# SHT1x.net
KiCad netlist of a schematic drawn in Altium Designer
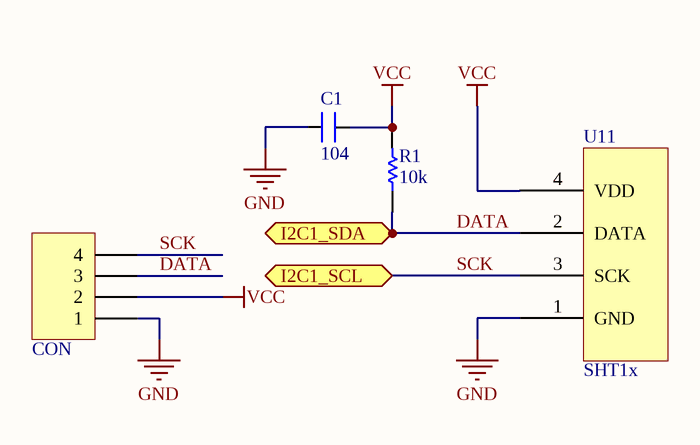
[diagram p0: SHT1x.SchDoc]

(export (version "E")
  (design (tool "Eeschema 10.0.6"))
  (components
    (comp (ref "C1")
      (value "104")
      (footprint "CAPC1608N")
      (fields (field (name "Comment") "CAP NP"))
      (libsource (lib "Tuan") (part "CAP NP"))
    )
    (comp (ref "CON")
      (value "Header 4H")
      (footprint "heromap:HDR1X4H")
      (description "Header, 4-Pin, Right Angle")
      (fields (field (name "PUBLISHER") "Altium Limited"))
      (libsource (lib "heromap") (part "Header 4H"))
    )
    (comp (ref "R1")
      (value "10k")
      (footprint "RESC2012N_F")
      (fields (field (name "Comment") "Res"))
      (libsource (lib "Tuan") (part "Res"))
    )
    (comp (ref "U11") (value "SHT1x") (footprint "SHT1x") (libsource (lib "Tuan") (part "SHT1x")))
  )
  (nets
    (net (code "1") (name "/DATA") (class "Default")
      (node (ref "CON") (pin "3") (pinfunction "3_3") (pintype "passive"))
      (node (ref "R1") (pin "1") (pinfunction "1_1") (pintype "passive"))
      (node (ref "U11") (pin "2") (pinfunction "DATA_2") (pintype "passive"))
    )
    (net (code "2") (name "/SCK") (class "Default")
      (node (ref "CON") (pin "4") (pinfunction "4_4") (pintype "passive"))
      (node (ref "U11") (pin "3") (pinfunction "SCK_3") (pintype "passive"))
    )
    (net (code "3") (name "GND") (class "Default")
      (node (ref "C1") (pin "2") (pinfunction "2_2") (pintype "passive"))
      (node (ref "CON") (pin "1") (pinfunction "1_1") (pintype "passive"))
      (node (ref "U11") (pin "1") (pinfunction "GND_1") (pintype "passive"))
    )
    (net (code "4") (name "VCC") (class "Default")
      (node (ref "C1") (pin "1") (pinfunction "1_1") (pintype "passive"))
      (node (ref "CON") (pin "2") (pinfunction "2_2") (pintype "passive"))
      (node (ref "R1") (pin "2") (pinfunction "2_2") (pintype "passive"))
      (node (ref "U11") (pin "4") (pinfunction "VDD_4") (pintype "passive"))
    )
  )
)
